# v1_2.net
KiCad netlist of a schematic drawn in Altium Designer
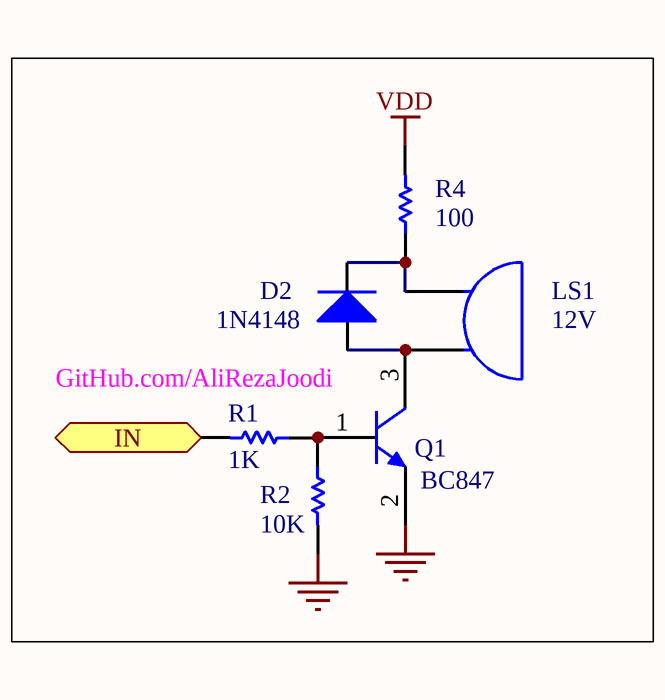
[diagram p0: v1.2.SchDoc]

(export (version "E")
  (design (tool "Eeschema 10.0.6"))
  (components
    (comp (ref "D2")
      (value "1N4148")
      (footprint "SOD-523")
      (description "Default Diode")
      (fields
        (field (name "MANUFACTURER") "Generic Components")
        (field (name "Comment") "Diode")
        (field (name "PUBLISHER") "Altium Limited")
      )
      (libsource (lib "Miscellaneous Devices") (part "Diode"))
    )
    (comp (ref "LS1")
      (value "12V")
      (footprint "RB_7.62mm")
      (description "Sounder")
      (fields
        (field (name "MANUFACTURER") "Generic Components")
        (field (name "Comment") "Buzzer")
        (field (name "PUBLISHER") "Altium Limited")
      )
      (libsource (lib "my Libraries") (part "Buzzer"))
    )
    (comp (ref "Q1")
      (value "BC847")
      (footprint "SOT23-3N")
      (description "Silicon Bipolar Transistor")
      (fields (field (name "Comment") "NPN"))
      (libsource (lib "my Libraries") (part "BC847"))
    )
    (comp (ref "R1")
      (value "1K")
      (footprint "0805")
      (description "Resistor")
      (fields (field (name "Comment") "Res1") (field (name "PUBLISHER") "Altium Limited"))
      (libsource (lib "Miscellaneous Devices") (part "Res1"))
    )
    (comp (ref "R2")
      (value "10K")
      (footprint "0805")
      (description "Resistor")
      (fields (field (name "Comment") "Res1") (field (name "PUBLISHER") "Altium Limited"))
      (libsource (lib "Miscellaneous Devices") (part "Res1"))
    )
    (comp (ref "R4")
      (value "100")
      (footprint "0805")
      (description "Resistor")
      (fields (field (name "Comment") "Res1") (field (name "PUBLISHER") "Altium Limited"))
      (libsource (lib "Miscellaneous Devices") (part "Res1"))
    )
  )
  (nets
    (net (code "1") (name "/IN") (class "Default")
      (node (ref "R1") (pin "2") (pinfunction "2_2") (pintype "passive"))
    )
    (net (code "2") (name "GND") (class "Default")
      (node (ref "Q1") (pin "2") (pinfunction "E_2") (pintype "passive"))
      (node (ref "R2") (pin "2") (pinfunction "2_2") (pintype "passive"))
    )
    (net (code "3") (name "Net-(D2-A)") (class "Default")
      (node (ref "D2") (pin "1") (pinfunction "A_1") (pintype "passive"))
      (node (ref "LS1") (pin "2") (pinfunction "B_2") (pintype "passive"))
      (node (ref "Q1") (pin "3") (pinfunction "C_3") (pintype "passive"))
    )
    (net (code "4") (name "Net-(D2-K)") (class "Default")
      (node (ref "D2") (pin "2") (pinfunction "K_2") (pintype "passive"))
      (node (ref "LS1") (pin "1") (pinfunction "A_1") (pintype "passive"))
      (node (ref "R4") (pin "1") (pinfunction "1_1") (pintype "passive"))
    )
    (net (code "5") (name "Net-(Q1-B)") (class "Default")
      (node (ref "Q1") (pin "1") (pinfunction "B_1") (pintype "passive"))
      (node (ref "R1") (pin "1") (pinfunction "1_1") (pintype "passive"))
      (node (ref "R2") (pin "1") (pinfunction "1_1") (pintype "passive"))
    )
    (net (code "6") (name "VDD") (class "Default")
      (node (ref "R4") (pin "2") (pinfunction "2_2") (pintype "passive"))
    )
  )
)
